# IMD.net
KiCad netlist of a schematic drawn in Altium Designer
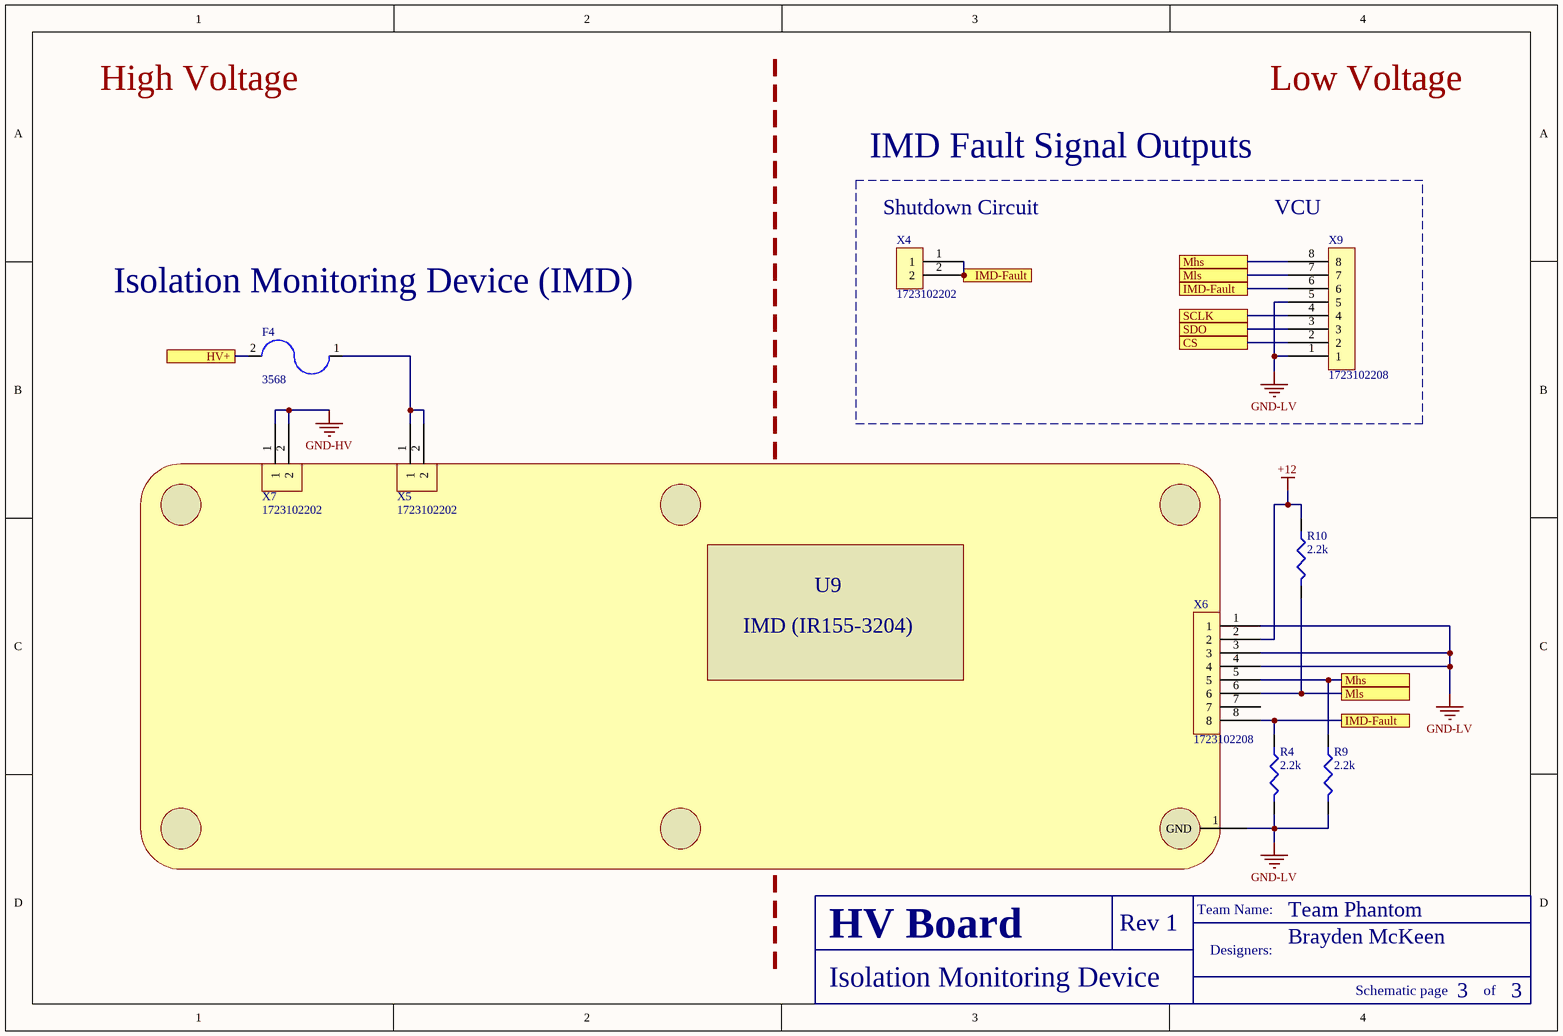
[diagram p0: IMD.SchDoc]

(export (version "E")
  (design (tool "Eeschema 10.0.6"))
  (components
    (comp (ref "F4")
      (value "3568")
      (footprint "FUSE_MINI_HOLDER")
      (description "FUSE HOLDER MINI AUTO PC")
      (fields (field (name "MANUFACTURER") "Keystone Electronics") (field (name "VOLTAGE") "500V"))
      (libsource (lib "PHANTOM_LIBRARY") (part "3568"))
    )
    (comp (ref "R4")
      (value "2.2k")
      (footprint "R0805")
      (description "RES SMD 2.2K OHM 5% 1/8W")
      (fields
        (field (name "MANUFACTURER") "Yageo")
        (field (name "MANUFACTURER PART NUMBER") "RC0805JR-072K2L")
      )
      (libsource (lib "PHANTOM_LIBRARY") (part "RC0805JR-072K2L"))
    )
    (comp (ref "R9")
      (value "2.2k")
      (footprint "R0805")
      (description "RES SMD 2.2K OHM 5% 1/8W")
      (fields
        (field (name "MANUFACTURER") "Yageo")
        (field (name "MANUFACTURER PART NUMBER") "RC0805JR-072K2L")
      )
      (libsource (lib "PHANTOM_LIBRARY") (part "RC0805JR-072K2L"))
    )
    (comp (ref "R10")
      (value "2.2k")
      (footprint "R0805")
      (description "RES SMD 2.2K OHM 5% 1/8W")
      (fields
        (field (name "MANUFACTURER") "Yageo")
        (field (name "MANUFACTURER PART NUMBER") "RC0805JR-072K2L")
      )
      (libsource (lib "PHANTOM_LIBRARY") (part "RC0805JR-072K2L"))
    )
    (comp (ref "U9")
      (value "IMD (IR155-3204)")
      (footprint "IR155-3204")
      (description "Isolation Monitoring Device (IMD) IR155-3204")
      (fields (field (name "MANUFACTURER") "Bender"))
      (libsource (lib "PHANTOM_LIBRARY") (part "IR155-3204"))
    )
    (comp (ref "X4")
      (value "1723102202")
      (footprint "Molex2Pin")
      (description "CONN HEADER R/A 2POS 3.5MM")
      (fields (field (name "MANUFACTURER") "Molex"))
      (libsource (lib "") (part "1723102202_1"))
    )
    (comp (ref "X5")
      (value "1723102202")
      (footprint "Molex2Pin")
      (description "CONN HEADER R/A 2POS 3.5MM")
      (fields (field (name "MANUFACTURER") "Molex"))
      (libsource (lib "PHANTOM_LIBRARY") (part "1723102202"))
    )
    (comp (ref "X6")
      (value "1723102208")
      (footprint "Molex8Pin")
      (description "CONN HEADER R/A 8POS 3.5MM")
      (fields (field (name "MANUFACTURER") "Molex"))
      (libsource (lib "") (part "1723102208_1"))
    )
    (comp (ref "X7")
      (value "1723102202")
      (footprint "Molex2Pin")
      (description "CONN HEADER R/A 2POS 3.5MM")
      (fields (field (name "MANUFACTURER") "Molex"))
      (libsource (lib "PHANTOM_LIBRARY") (part "1723102202"))
    )
    (comp (ref "X9")
      (value "1723102208")
      (footprint "Molex8Pin")
      (description "CONN HEADER R/A 8POS 3.5MM")
      (fields (field (name "MANUFACTURER") "Molex"))
      (libsource (lib "PHANTOM_LIBRARY") (part "1723102208"))
    )
  )
  (nets
    (net (code "1") (name "+12") (class "Default")
      (node (ref "R10") (pin "1") (pinfunction "1_1") (pintype "passive"))
      (node (ref "X6") (pin "2") (pinfunction "2_2") (pintype "passive"))
    )
    (net (code "2") (name "/CS") (class "Default")
      (node (ref "X9") (pin "2") (pinfunction "2_2") (pintype "passive"))
    )
    (net (code "3") (name "/HV+") (class "Default")
      (node (ref "F4") (pin "2") (pinfunction "2_2") (pintype "passive"))
    )
    (net (code "4") (name "/IMD-Fault") (class "Default")
      (node (ref "R4") (pin "1") (pinfunction "1_1") (pintype "passive"))
      (node (ref "X4") (pin "1") (pinfunction "1_1") (pintype "passive"))
      (node (ref "X4") (pin "2") (pinfunction "2_2") (pintype "passive"))
      (node (ref "X6") (pin "8") (pinfunction "8_8") (pintype "passive"))
      (node (ref "X9") (pin "6") (pinfunction "6_6") (pintype "passive"))
    )
    (net (code "5") (name "/Mhs") (class "Default")
      (node (ref "R9") (pin "1") (pinfunction "1_1") (pintype "passive"))
      (node (ref "X6") (pin "5") (pinfunction "5_5") (pintype "passive"))
      (node (ref "X9") (pin "8") (pinfunction "8_8") (pintype "passive"))
    )
    (net (code "6") (name "/Mls") (class "Default")
      (node (ref "R10") (pin "2") (pinfunction "2_2") (pintype "passive"))
      (node (ref "X6") (pin "6") (pinfunction "6_6") (pintype "passive"))
      (node (ref "X9") (pin "7") (pinfunction "7_7") (pintype "passive"))
    )
    (net (code "7") (name "/SCLK") (class "Default")
      (node (ref "X9") (pin "4") (pinfunction "4_4") (pintype "passive"))
    )
    (net (code "8") (name "/SDO") (class "Default")
      (node (ref "X9") (pin "3") (pinfunction "3_3") (pintype "passive"))
    )
    (net (code "9") (name "GND-HV") (class "Default")
      (node (ref "X7") (pin "1") (pinfunction "1_1") (pintype "passive"))
      (node (ref "X7") (pin "2") (pinfunction "2_2") (pintype "passive"))
    )
    (net (code "10") (name "GND-LV") (class "Default")
      (node (ref "R4") (pin "2") (pinfunction "2_2") (pintype "passive"))
      (node (ref "R9") (pin "2") (pinfunction "2_2") (pintype "passive"))
      (node (ref "U9") (pin "1") (pinfunction "GND_1") (pintype "passive"))
      (node (ref "X6") (pin "1") (pinfunction "1_1") (pintype "passive"))
      (node (ref "X6") (pin "3") (pinfunction "3_3") (pintype "passive"))
      (node (ref "X6") (pin "4") (pinfunction "4_4") (pintype "passive"))
      (node (ref "X9") (pin "1") (pinfunction "1_1") (pintype "passive"))
      (node (ref "X9") (pin "5") (pinfunction "5_5") (pintype "passive"))
    )
    (net (code "11") (name "Net-(F4-Pad1)") (class "Default")
      (node (ref "F4") (pin "1") (pinfunction "1_1") (pintype "passive"))
      (node (ref "X5") (pin "1") (pinfunction "1_1") (pintype "passive"))
      (node (ref "X5") (pin "2") (pinfunction "2_2") (pintype "passive"))
    )
    (net (code "12") (name "unconnected-(X6-Pad7)") (class "Default")
      (node (ref "X6") (pin "7") (pinfunction "7_7") (pintype "passive"))
    )
  )
)
